# Ethernet.net
KiCad netlist of a schematic drawn in Altium Designer
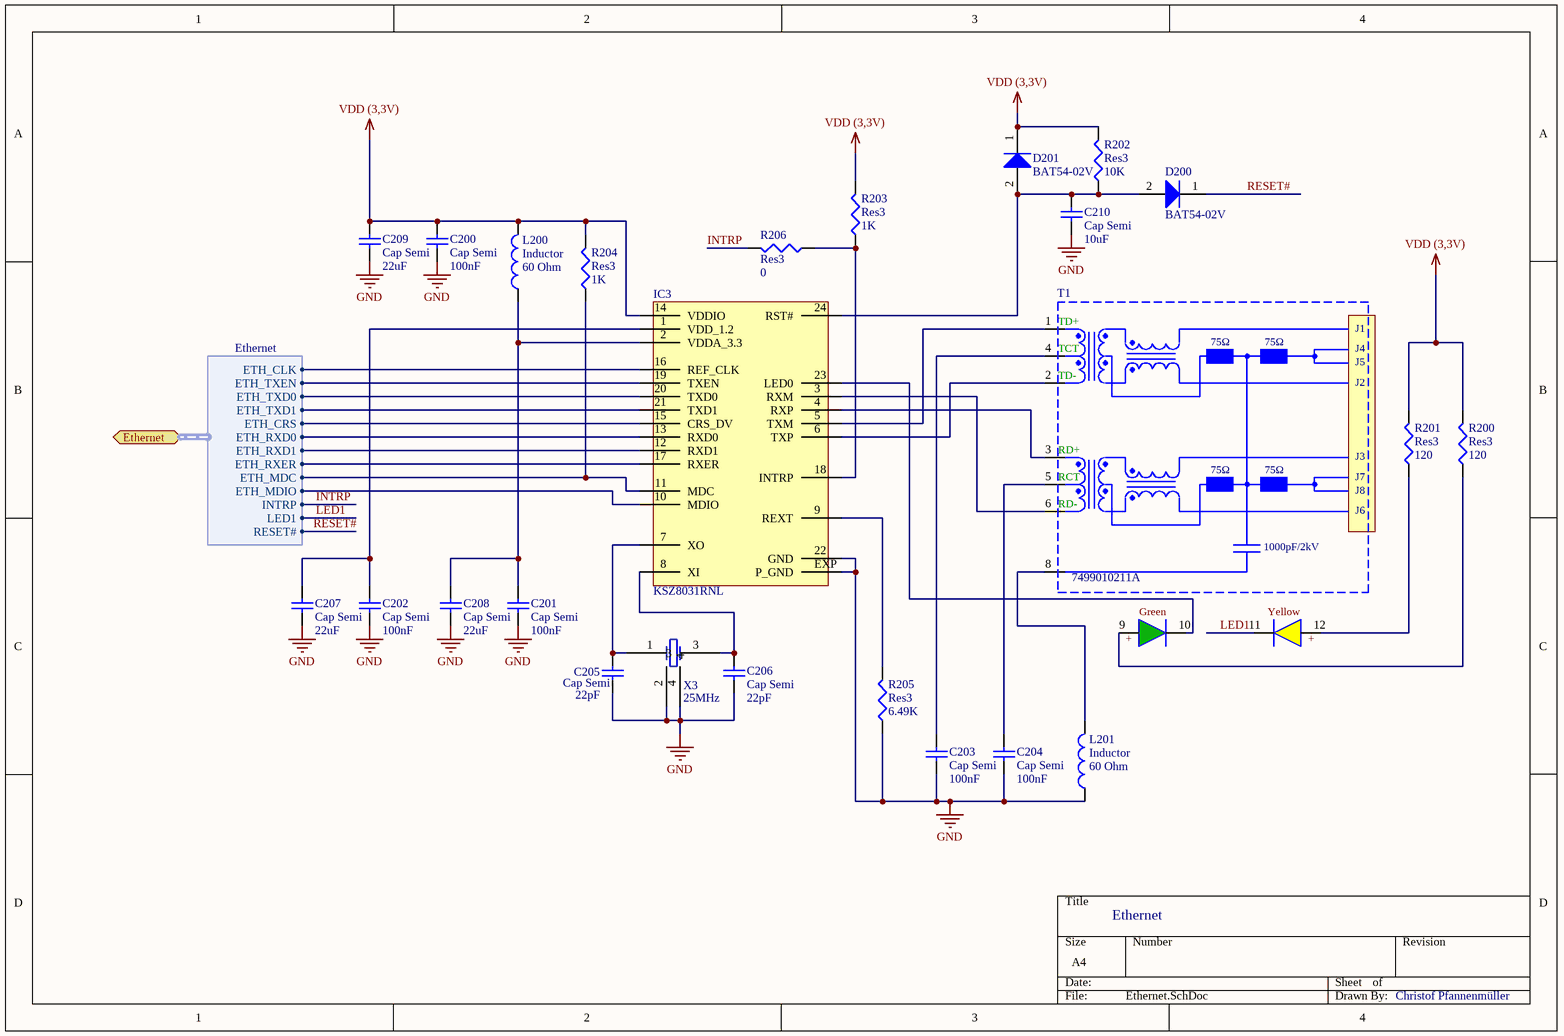
[diagram p0: Ethernet.SchDoc]

(export (version "E")
  (design (tool "Eeschema 10.0.6"))
  (components
    (comp (ref "C200")
      (value "Cap Semi")
      (footprint "0402")
      (description "Capacitor (Semiconductor SIM Model)")
      (fields (field (name "ALTIUM_VALUE") "100nF") (field (name "PUBLISHER") "Altium Limited"))
      (libsource (lib "Miscellaneous Devices") (part "Cap Semi"))
    )
    (comp (ref "C201")
      (value "Cap Semi")
      (footprint "0402")
      (description "Capacitor (Semiconductor SIM Model)")
      (fields (field (name "ALTIUM_VALUE") "100nF") (field (name "PUBLISHER") "Altium Limited"))
      (libsource (lib "Miscellaneous Devices") (part "Cap Semi"))
    )
    (comp (ref "C202")
      (value "Cap Semi")
      (footprint "C1206")
      (description "Capacitor (Semiconductor SIM Model)")
      (fields (field (name "ALTIUM_VALUE") "100nF") (field (name "PUBLISHER") "Altium Limited"))
      (libsource (lib "Miscellaneous Devices") (part "Cap Semi"))
    )
    (comp (ref "C203")
      (value "Cap Semi")
      (footprint "C1206")
      (description "Capacitor (Semiconductor SIM Model)")
      (fields (field (name "ALTIUM_VALUE") "100nF") (field (name "PUBLISHER") "Altium Limited"))
      (libsource (lib "Miscellaneous Devices") (part "Cap Semi"))
    )
    (comp (ref "C204")
      (value "Cap Semi")
      (footprint "C1206")
      (description "Capacitor (Semiconductor SIM Model)")
      (fields (field (name "ALTIUM_VALUE") "100nF") (field (name "PUBLISHER") "Altium Limited"))
      (libsource (lib "Miscellaneous Devices") (part "Cap Semi"))
    )
    (comp (ref "C205")
      (value "Cap Semi")
      (footprint "0402")
      (description "Capacitor (Semiconductor SIM Model)")
      (fields (field (name "ALTIUM_VALUE") "22pF") (field (name "PUBLISHER") "Altium Limited"))
      (libsource (lib "Miscellaneous Devices") (part "Cap Semi"))
    )
    (comp (ref "C206")
      (value "Cap Semi")
      (footprint "0402")
      (description "Capacitor (Semiconductor SIM Model)")
      (fields (field (name "ALTIUM_VALUE") "22pF") (field (name "PUBLISHER") "Altium Limited"))
      (libsource (lib "Miscellaneous Devices") (part "Cap Semi"))
    )
    (comp (ref "C207")
      (value "Cap Semi")
      (footprint "C1206")
      (description "Capacitor (Semiconductor SIM Model)")
      (fields (field (name "ALTIUM_VALUE") "22uF") (field (name "PUBLISHER") "Altium Limited"))
      (libsource (lib "Miscellaneous Devices") (part "Cap Semi"))
    )
    (comp (ref "C208")
      (value "Cap Semi")
      (footprint "C1206")
      (description "Capacitor (Semiconductor SIM Model)")
      (fields (field (name "ALTIUM_VALUE") "22uF") (field (name "PUBLISHER") "Altium Limited"))
      (libsource (lib "Miscellaneous Devices") (part "Cap Semi"))
    )
    (comp (ref "C209")
      (value "Cap Semi")
      (footprint "C1206")
      (description "Capacitor (Semiconductor SIM Model)")
      (fields (field (name "ALTIUM_VALUE") "22uF") (field (name "PUBLISHER") "Altium Limited"))
      (libsource (lib "Miscellaneous Devices") (part "Cap Semi"))
    )
    (comp (ref "C210")
      (value "Cap Semi")
      (footprint "C1206")
      (description "Capacitor (Semiconductor SIM Model)")
      (fields (field (name "ALTIUM_VALUE") "10uF") (field (name "PUBLISHER") "Altium Limited"))
      (libsource (lib "Miscellaneous Devices") (part "Cap Semi"))
    )
    (comp (ref "D200")
      (value "BAT54-02V")
      (footprint "INF-SC79_V")
      (description "Silicon Schottky Diode, SC79, Reel, Green")
      (fields (field (name "MANUFACTURER") "Infineon"))
      (libsource (lib "Infineon_Transistor_&_Diode") (part "BAT54-02V"))
    )
    (comp (ref "D201")
      (value "BAT54-02V")
      (footprint "INF-SC79_V")
      (description "Silicon Schottky Diode, SC79, Reel, Green")
      (fields (field (name "MANUFACTURER") "Infineon"))
      (libsource (lib "Infineon_Transistor_&_Diode") (part "BAT54-02V"))
    )
    (comp (ref "IC3")
      (value "KSZ8031RNL")
      (footprint "QFN /MLF 24pin")
      (libsource (lib "Schematic library") (part "KSZ8031RNL"))
    )
    (comp (ref "L200")
      (value "Inductor")
      (footprint "0603")
      (fields (field (name "ALTIUM_VALUE") "60 Ohm") (field (name "PUBLISHER") "Altium Limited"))
      (libsource (lib "Miscellaneous Devices") (part "Inductor"))
    )
    (comp (ref "L201")
      (value "Inductor")
      (footprint "0603")
      (fields (field (name "ALTIUM_VALUE") "60 Ohm") (field (name "PUBLISHER") "Altium Limited"))
      (libsource (lib "Miscellaneous Devices") (part "Inductor"))
    )
    (comp (ref "R200")
      (value "Res3")
      (footprint "J1-0603")
      (description "Resistor")
      (fields (field (name "ALTIUM_VALUE") "120") (field (name "PUBLISHER") "Altium Limited"))
      (libsource (lib "Miscellaneous Devices") (part "Res3"))
    )
    (comp (ref "R201")
      (value "Res3")
      (footprint "J1-0603")
      (description "Resistor")
      (fields (field (name "ALTIUM_VALUE") "120") (field (name "PUBLISHER") "Altium Limited"))
      (libsource (lib "Miscellaneous Devices") (part "Res3"))
    )
    (comp (ref "R202")
      (value "Res3")
      (footprint "J1-0603")
      (description "Resistor")
      (fields (field (name "ALTIUM_VALUE") "10K") (field (name "PUBLISHER") "Altium Limited"))
      (libsource (lib "Miscellaneous Devices") (part "Res3"))
    )
    (comp (ref "R203")
      (value "Res3")
      (footprint "J1-0603")
      (description "Resistor")
      (fields (field (name "ALTIUM_VALUE") "1K") (field (name "PUBLISHER") "Altium Limited"))
      (libsource (lib "Miscellaneous Devices") (part "Res3"))
    )
    (comp (ref "R204")
      (value "Res3")
      (footprint "J1-0603")
      (description "Resistor")
      (fields (field (name "ALTIUM_VALUE") "1K") (field (name "PUBLISHER") "Altium Limited"))
      (libsource (lib "Miscellaneous Devices") (part "Res3"))
    )
    (comp (ref "R205")
      (value "Res3")
      (footprint "J1-0603")
      (description "Resistor")
      (fields (field (name "ALTIUM_VALUE") "6.49K") (field (name "PUBLISHER") "Altium Limited"))
      (libsource (lib "Miscellaneous Devices") (part "Res3"))
    )
    (comp (ref "R206")
      (value "Res3")
      (footprint "J1-0603")
      (description "Resistor")
      (fields (field (name "ALTIUM_VALUE") "0") (field (name "PUBLISHER") "Altium Limited"))
      (libsource (lib "Miscellaneous Devices") (part "Res3"))
    )
    (comp (ref "T1")
      (value "7499010211A")
      (footprint "7499010211A")
      (description "RJ45 LAN Transformer, 10/100 Base-T")
      (fields (field (name "MANUFACTURER") "Wurth Elektronik") (field (name "CREATED BY") "Baojun Chen"))
      (libsource (lib "WE-RJ45_LAN_rev16b") (part "7499010211A"))
    )
    (comp (ref "X3") (value "25MHz") (footprint "Quarz") (libsource (lib "Schlib1") (part "Quarz")))
  )
  (nets
    (net (code "2") (name "/ETH_CLK") (class "Default")
      (node (ref "IC3") (pin "16") (pinfunction "REF_CLK_16") (pintype "passive"))
    )
    (net (code "3") (name "/ETH_CRS") (class "Default")
      (node (ref "IC3") (pin "15") (pinfunction "CRS_DV_15") (pintype "passive"))
    )
    (net (code "4") (name "/ETH_MDC") (class "Default")
      (node (ref "IC3") (pin "11") (pinfunction "MDC_11") (pintype "passive"))
      (node (ref "R204") (pin "1") (pinfunction "1_1") (pintype "passive"))
    )
    (net (code "5") (name "/ETH_MDIO") (class "Default")
      (node (ref "IC3") (pin "10") (pinfunction "MDIO_10") (pintype "passive"))
    )
    (net (code "6") (name "/ETH_RXD0") (class "Default")
      (node (ref "IC3") (pin "13") (pinfunction "RXD0_13") (pintype "passive"))
    )
    (net (code "7") (name "/ETH_RXD1") (class "Default")
      (node (ref "IC3") (pin "12") (pinfunction "RXD1_12") (pintype "passive"))
    )
    (net (code "8") (name "/ETH_RXER") (class "Default")
      (node (ref "IC3") (pin "17") (pinfunction "RXER_17") (pintype "passive"))
    )
    (net (code "9") (name "/ETH_TXD0") (class "Default")
      (node (ref "IC3") (pin "20") (pinfunction "TXD0_20") (pintype "passive"))
    )
    (net (code "10") (name "/ETH_TXD1") (class "Default")
      (node (ref "IC3") (pin "21") (pinfunction "TXD1_21") (pintype "passive"))
    )
    (net (code "11") (name "/ETH_TXEN") (class "Default")
      (node (ref "IC3") (pin "19") (pinfunction "TXEN_19") (pintype "passive"))
    )
    (net (code "12") (name "/INTRP") (class "Default")
      (node (ref "R206") (pin "2") (pinfunction "2_2") (pintype "passive"))
    )
    (net (code "13") (name "/LED1") (class "Default")
      (node (ref "T1") (pin "11") (pinfunction "11_11") (pintype "passive"))
    )
    (net (code "14") (name "/RESET#") (class "Default")
      (node (ref "D200") (pin "1") (pinfunction "K_1") (pintype "passive"))
    )
    (net (code "16") (name "GND") (class "Default")
      (node (ref "C200") (pin "1") (pinfunction "1_1") (pintype "passive"))
      (node (ref "C201") (pin "1") (pinfunction "1_1") (pintype "passive"))
      (node (ref "C202") (pin "1") (pinfunction "1_1") (pintype "passive"))
      (node (ref "C203") (pin "1") (pinfunction "1_1") (pintype "passive"))
      (node (ref "C204") (pin "1") (pinfunction "1_1") (pintype "passive"))
      (node (ref "C205") (pin "1") (pinfunction "1_1") (pintype "passive"))
      (node (ref "C206") (pin "1") (pinfunction "1_1") (pintype "passive"))
      (node (ref "C207") (pin "1") (pinfunction "1_1") (pintype "passive"))
      (node (ref "C208") (pin "1") (pinfunction "1_1") (pintype "passive"))
      (node (ref "C209") (pin "1") (pinfunction "1_1") (pintype "passive"))
      (node (ref "C210") (pin "1") (pinfunction "1_1") (pintype "passive"))
      (node (ref "IC3") (pin "22") (pinfunction "GND_22") (pintype "passive"))
      (node (ref "IC3") (pin "EXP") (pinfunction "P_GND_EXP") (pintype "passive"))
      (node (ref "L201") (pin "1") (pinfunction "1_1") (pintype "passive"))
      (node (ref "R205") (pin "1") (pinfunction "1_1") (pintype "passive"))
      (node (ref "X3") (pin "2") (pinfunction "2_2") (pintype "passive"))
      (node (ref "X3") (pin "4") (pinfunction "4_4") (pintype "passive"))
    )
    (net (code "17") (name "Net-(D200-A)") (class "Default")
      (node (ref "C210") (pin "2") (pinfunction "2_2") (pintype "passive"))
      (node (ref "D200") (pin "2") (pinfunction "A_2") (pintype "passive"))
      (node (ref "D201") (pin "2") (pinfunction "A_2") (pintype "passive"))
      (node (ref "IC3") (pin "24") (pinfunction "RST#_24") (pintype "passive"))
      (node (ref "R202") (pin "1") (pinfunction "1_1") (pintype "passive"))
    )
    (net (code "18") (name "Net-(IC3-INTRP)") (class "Default")
      (node (ref "IC3") (pin "18") (pinfunction "INTRP_18") (pintype "passive"))
      (node (ref "R203") (pin "1") (pinfunction "1_1") (pintype "passive"))
      (node (ref "R206") (pin "1") (pinfunction "1_1") (pintype "passive"))
    )
    (net (code "19") (name "Net-(IC3-LED0)") (class "Default")
      (node (ref "IC3") (pin "23") (pinfunction "LED0_23") (pintype "passive"))
      (node (ref "T1") (pin "10") (pinfunction "10_10") (pintype "passive"))
    )
    (net (code "20") (name "Net-(IC3-REXT)") (class "Default")
      (node (ref "IC3") (pin "9") (pinfunction "REXT_9") (pintype "passive"))
      (node (ref "R205") (pin "2") (pinfunction "2_2") (pintype "passive"))
    )
    (net (code "21") (name "Net-(IC3-RXM)") (class "Default")
      (node (ref "IC3") (pin "3") (pinfunction "RXM_3") (pintype "passive"))
      (node (ref "T1") (pin "6") (pinfunction "RD-_6") (pintype "passive"))
    )
    (net (code "22") (name "Net-(IC3-RXP)") (class "Default")
      (node (ref "IC3") (pin "4") (pinfunction "RXP_4") (pintype "passive"))
      (node (ref "T1") (pin "3") (pinfunction "TD-_3") (pintype "passive"))
    )
    (net (code "23") (name "Net-(IC3-TXM)") (class "Default")
      (node (ref "IC3") (pin "5") (pinfunction "TXM_5") (pintype "passive"))
      (node (ref "T1") (pin "1") (pinfunction "TD+_1") (pintype "passive"))
    )
    (net (code "24") (name "Net-(IC3-TXP)") (class "Default")
      (node (ref "IC3") (pin "6") (pinfunction "TXP_6") (pintype "passive"))
      (node (ref "T1") (pin "2") (pinfunction "TCT_2") (pintype "passive"))
    )
    (net (code "25") (name "Net-(IC3-VDDA_3.3)") (class "Default")
      (node (ref "C201") (pin "2") (pinfunction "2_2") (pintype "passive"))
      (node (ref "C208") (pin "2") (pinfunction "2_2") (pintype "passive"))
      (node (ref "IC3") (pin "2") (pinfunction "VDDA_3.3_2") (pintype "passive"))
      (node (ref "L200") (pin "1") (pinfunction "1_1") (pintype "passive"))
    )
    (net (code "26") (name "Net-(IC3-VDD_1.2)") (class "Default")
      (node (ref "C202") (pin "2") (pinfunction "2_2") (pintype "passive"))
      (node (ref "C207") (pin "2") (pinfunction "2_2") (pintype "passive"))
      (node (ref "IC3") (pin "1") (pinfunction "VDD_1.2_1") (pintype "passive"))
    )
    (net (code "27") (name "Net-(IC3-XI)") (class "Default")
      (node (ref "C206") (pin "2") (pinfunction "2_2") (pintype "passive"))
      (node (ref "IC3") (pin "8") (pinfunction "XI_8") (pintype "passive"))
      (node (ref "X3") (pin "3") (pinfunction "3_3") (pintype "passive"))
    )
    (net (code "28") (name "Net-(IC3-XO)") (class "Default")
      (node (ref "C205") (pin "2") (pinfunction "2_2") (pintype "passive"))
      (node (ref "IC3") (pin "7") (pinfunction "XO_7") (pintype "passive"))
      (node (ref "X3") (pin "1") (pinfunction "1_1") (pintype "passive"))
    )
    (net (code "29") (name "Net-(L201-Pad2)") (class "Default")
      (node (ref "L201") (pin "2") (pinfunction "2_2") (pintype "passive"))
      (node (ref "T1") (pin "8") (pinfunction "8_8") (pintype "passive"))
    )
    (net (code "30") (name "Net-(R200-Pad1)") (class "Default")
      (node (ref "R200") (pin "1") (pinfunction "1_1") (pintype "passive"))
      (node (ref "T1") (pin "9") (pinfunction "9_9") (pintype "passive"))
    )
    (net (code "31") (name "Net-(R201-Pad1)") (class "Default")
      (node (ref "R201") (pin "1") (pinfunction "1_1") (pintype "passive"))
      (node (ref "T1") (pin "12") (pinfunction "12_12") (pintype "passive"))
    )
    (net (code "32") (name "Net-(T1-RCT)") (class "Default")
      (node (ref "C204") (pin "2") (pinfunction "2_2") (pintype "passive"))
      (node (ref "T1") (pin "5") (pinfunction "RCT_5") (pintype "passive"))
    )
    (net (code "33") (name "Net-(T1-RD+)") (class "Default")
      (node (ref "C203") (pin "2") (pinfunction "2_2") (pintype "passive"))
      (node (ref "T1") (pin "4") (pinfunction "RD+_4") (pintype "passive"))
    )
    (net (code "34") (name "VDD (3,3V)") (class "Default")
      (node (ref "C200") (pin "2") (pinfunction "2_2") (pintype "passive"))
      (node (ref "C209") (pin "2") (pinfunction "2_2") (pintype "passive"))
      (node (ref "D201") (pin "1") (pinfunction "K_1") (pintype "passive"))
      (node (ref "IC3") (pin "14") (pinfunction "VDDIO_14") (pintype "passive"))
      (node (ref "L200") (pin "2") (pinfunction "2_2") (pintype "passive"))
      (node (ref "R200") (pin "2") (pinfunction "2_2") (pintype "passive"))
      (node (ref "R201") (pin "2") (pinfunction "2_2") (pintype "passive"))
      (node (ref "R202") (pin "2") (pinfunction "2_2") (pintype "passive"))
      (node (ref "R203") (pin "2") (pinfunction "2_2") (pintype "passive"))
      (node (ref "R204") (pin "2") (pinfunction "2_2") (pintype "passive"))
    )
  )
)
